# CPU.net
KiCad netlist of a schematic drawn in Altium Designer
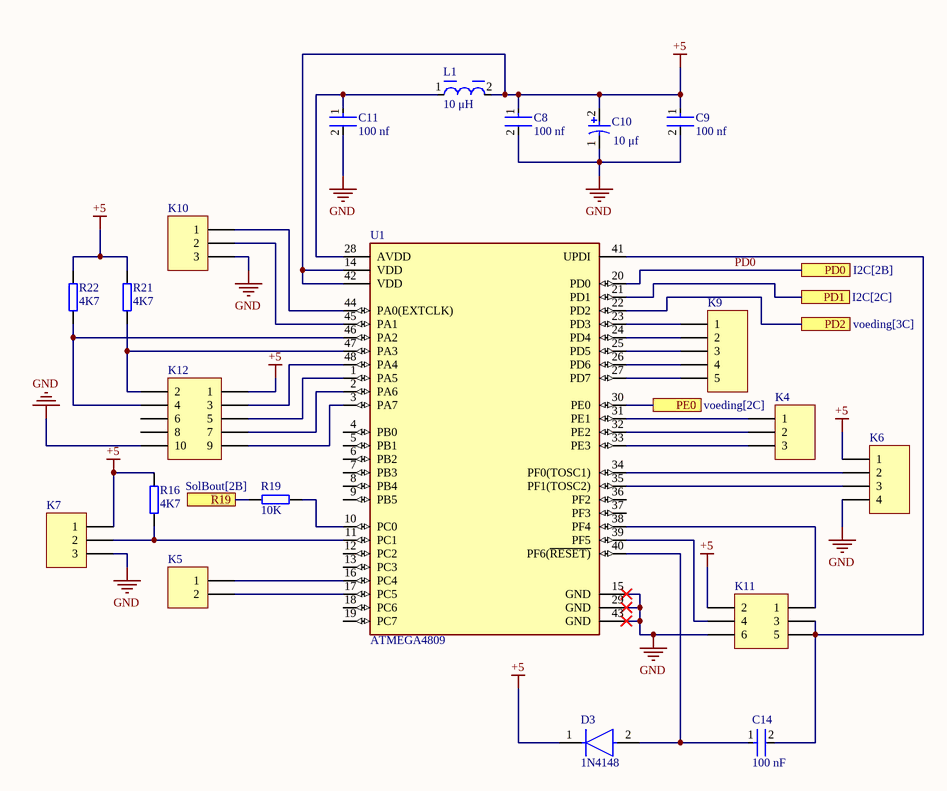
[diagram p0: CPU.SchDoc]

(export (version "E")
  (design (tool "Eeschema 10.0.6"))
  (components
    (comp (ref "C8")
      (value "100 nf")
      (footprint "CC_0805_L")
      (fields
        (field (name "MANUFACTURER") "KEMET")
        (field (name "OCTOPART") "https://octopart.com/c0805c224k5ractu-kemet-144670")
        (field (name "MANUFACTURER PART NUMBER") "C0805C224K5RACTU")
      )
      (libsource (lib "Soldeerstation_Final") (part "Capacitor_Ceramic"))
    )
    (comp (ref "C9")
      (value "100 nf")
      (footprint "CC_0805_L")
      (fields
        (field (name "MANUFACTURER") "KEMET")
        (field (name "OCTOPART") "https://octopart.com/c0805c224k5ractu-kemet-144670")
        (field (name "MANUFACTURER PART NUMBER") "C0805C224K5RACTU")
      )
      (libsource (lib "Soldeerstation_Final") (part "Capacitor_Ceramic"))
    )
    (comp (ref "C10")
      (value "10 μf")
      (footprint "CE_D8_L10")
      (fields (field (name "MANUFACTURER") "Panasonic"))
      (libsource (lib "Soldeerstation_Final") (part "Capacitor_Electrolytic"))
    )
    (comp (ref "C11")
      (value "100 nf")
      (footprint "CC_0805_L")
      (fields
        (field (name "MANUFACTURER") "KEMET")
        (field (name "OCTOPART") "https://octopart.com/c0805c224k5ractu-kemet-144670")
        (field (name "MANUFACTURER PART NUMBER") "C0805C224K5RACTU")
      )
      (libsource (lib "Soldeerstation_Final") (part "Capacitor_Ceramic"))
    )
    (comp (ref "C14")
      (value "100 nF")
      (footprint "CC_0805_L")
      (fields
        (field (name "MANUFACTURER") "KEMET")
        (field (name "OCTOPART") "https://octopart.com/c0805c224k5ractu-kemet-144670")
        (field (name "MANUFACTURER PART NUMBER") "C0805C224K5RACTU")
      )
      (libsource (lib "Soldeerstation_Final") (part "Capacitor_Ceramic"))
    )
    (comp (ref "D3")
      (value "1N4148")
      (footprint "SOD-123FL")
      (fields
        (field (name "MANUFACTURER PART NUMBER") "1N4007")
        (field (name "MANUFACTURER") "Diotec")
        (field (name "OCTOPART") "https://octopart.com/1n4007-diotec-4040411")
      )
      (libsource (lib "Soldeerstation_Final") (part "Diode"))
    )
    (comp (ref "K4")
      (value "~")
      (footprint "HDR1X3")
      (description "Header, 3-Pin")
      (fields (field (name "PUBLISHER") "Altium Limited"))
      (libsource (lib "") (part "Header 3_1"))
    )
    (comp (ref "K5")
      (value "~")
      (footprint "HDR1X2")
      (description "Header, 2-Pin")
      (fields (field (name "PUBLISHER") "Altium Limited"))
      (libsource (lib "Miscellaneous Connectors") (part "Header 2"))
    )
    (comp (ref "K6")
      (value "~")
      (footprint "HDR1X4")
      (description "Header, 4-Pin")
      (fields (field (name "PUBLISHER") "Altium Limited"))
      (libsource (lib "Miscellaneous Connectors") (part "Header 4"))
    )
    (comp (ref "K7")
      (value "~")
      (footprint "HDR1X3")
      (description "Header, 3-Pin")
      (fields (field (name "PUBLISHER") "Altium Limited"))
      (libsource (lib "Miscellaneous Connectors") (part "Header 3"))
    )
    (comp (ref "K9")
      (value "~")
      (footprint "HDR1X5")
      (description "Header, 5-Pin")
      (fields (field (name "PUBLISHER") "Altium Limited"))
      (libsource (lib "Miscellaneous Connectors") (part "Header 5"))
    )
    (comp (ref "K10")
      (value "~")
      (footprint "HDR1X3")
      (description "Header, 3-Pin")
      (fields (field (name "PUBLISHER") "Altium Limited"))
      (libsource (lib "Miscellaneous Connectors") (part "Header 3"))
    )
    (comp (ref "K11")
      (value "~")
      (footprint "HDR2X3")
      (description "Header, 3-Pin, Dual row")
      (fields (field (name "PUBLISHER") "Altium Limited"))
      (libsource (lib "Miscellaneous Connectors") (part "Header 3X2"))
    )
    (comp (ref "K12")
      (value "~")
      (footprint "HDR2X5")
      (description "Header, 5-Pin, Dual row")
      (fields (field (name "PUBLISHER") "Altium Limited"))
      (libsource (lib "Miscellaneous Connectors") (part "Header 5X2"))
    )
    (comp (ref "L1")
      (value "10 μH")
      (footprint "CC_0805_L")
      (fields (field (name "TOLERANCE") "20%"))
      (libsource (lib "Soldeerstation_Final") (part "Choke"))
    )
    (comp (ref "R16")
      (value "4K7")
      (footprint "0805_M")
      (fields (field (name "MANUFACTURER") "Vishay Dale") (field (name "PART NUMBER") "CRCW08050000Z0EA"))
      (libsource (lib "Soldeerstation_Final") (part "Resistor"))
    )
    (comp (ref "R19")
      (value "10K")
      (footprint "0805_M")
      (fields (field (name "MANUFACTURER") "Vishay Dale") (field (name "PART NUMBER") "CRCW08050000Z0EA"))
      (libsource (lib "Soldeerstation_Final") (part "Resistor"))
    )
    (comp (ref "R21")
      (value "4K7")
      (footprint "0805_M")
      (fields (field (name "MANUFACTURER") "Vishay Dale") (field (name "PART NUMBER") "CRCW08050000Z0EA"))
      (libsource (lib "Soldeerstation_Final") (part "Resistor"))
    )
    (comp (ref "R22")
      (value "4K7")
      (footprint "0805_M")
      (fields (field (name "MANUFACTURER") "Vishay Dale") (field (name "PART NUMBER") "CRCW08050000Z0EA"))
      (libsource (lib "Soldeerstation_Final") (part "Resistor"))
    )
    (comp (ref "U1")
      (value "ATMEGA4809")
      (footprint "TQFP_48_M")
      (libsource (lib "Soldeerstation_Final") (part "ATMEGA4809"))
    )
  )
  (nets
    (net (code "1") (name "+5") (class "Default")
      (node (ref "C10") (pin "2") (pinfunction "2_2") (pintype "passive"))
      (node (ref "C8") (pin "1") (pinfunction "1_1") (pintype "passive"))
      (node (ref "C9") (pin "1") (pinfunction "1_1") (pintype "passive"))
      (node (ref "D3") (pin "1") (pinfunction "C_1") (pintype "passive"))
      (node (ref "K11") (pin "2") (pinfunction "2_2") (pintype "passive"))
      (node (ref "K12") (pin "1") (pinfunction "1_1") (pintype "passive"))
      (node (ref "K6") (pin "1") (pinfunction "1_1") (pintype "passive"))
      (node (ref "K7") (pin "1") (pinfunction "1_1") (pintype "passive"))
      (node (ref "L1") (pin "2") (pinfunction "2_2") (pintype "passive"))
      (node (ref "R16") (pin "2") (pinfunction "2_2") (pintype "passive"))
      (node (ref "R21") (pin "2") (pinfunction "2_2") (pintype "passive"))
      (node (ref "R22") (pin "2") (pinfunction "2_2") (pintype "passive"))
      (node (ref "U1") (pin "14") (pinfunction "VDD_14") (pintype "power_in"))
      (node (ref "U1") (pin "42") (pinfunction "VDD_42") (pintype "power_in"))
    )
    (net (code "2") (name "/PD0") (class "Default")
      (node (ref "U1") (pin "20") (pinfunction "PD0_20") (pintype "bidirectional"))
    )
    (net (code "3") (name "/PD1") (class "Default")
      (node (ref "U1") (pin "21") (pinfunction "PD1_21") (pintype "bidirectional"))
    )
    (net (code "4") (name "/PD2") (class "Default")
      (node (ref "U1") (pin "22") (pinfunction "PD2_22") (pintype "bidirectional"))
    )
    (net (code "5") (name "/PE0") (class "Default")
      (node (ref "U1") (pin "30") (pinfunction "PE0_30") (pintype "bidirectional"))
    )
    (net (code "6") (name "/R19") (class "Default")
      (node (ref "R19") (pin "1") (pinfunction "1_1") (pintype "passive"))
    )
    (net (code "7") (name "GND") (class "Default")
      (node (ref "C10") (pin "1") (pinfunction "1_1") (pintype "passive"))
      (node (ref "C11") (pin "2") (pinfunction "2_2") (pintype "passive"))
      (node (ref "C8") (pin "2") (pinfunction "2_2") (pintype "passive"))
      (node (ref "C9") (pin "2") (pinfunction "2_2") (pintype "passive"))
      (node (ref "K10") (pin "3") (pinfunction "3_3") (pintype "passive"))
      (node (ref "K11") (pin "6") (pinfunction "6_6") (pintype "passive"))
      (node (ref "K12") (pin "10") (pinfunction "10_10") (pintype "passive"))
      (node (ref "K6") (pin "4") (pinfunction "4_4") (pintype "passive"))
      (node (ref "K7") (pin "3") (pinfunction "3_3") (pintype "passive"))
      (node (ref "U1") (pin "15") (pinfunction "GND_15") (pintype "open_emitter"))
      (node (ref "U1") (pin "29") (pinfunction "GND_29") (pintype "power_in"))
      (node (ref "U1") (pin "43") (pinfunction "GND_43") (pintype "power_in"))
    )
    (net (code "8") (name "Net-(D3-A)") (class "Default")
      (node (ref "C14") (pin "1") (pinfunction "1_1") (pintype "passive"))
      (node (ref "D3") (pin "2") (pinfunction "A_2") (pintype "passive"))
      (node (ref "U1") (pin "40") (pinfunction "PF6(~{RESET)}_40") (pintype "bidirectional"))
    )
    (net (code "9") (name "Net-(U1-AVDD)") (class "Default")
      (node (ref "C11") (pin "1") (pinfunction "1_1") (pintype "passive"))
      (node (ref "L1") (pin "1") (pinfunction "1_1") (pintype "passive"))
      (node (ref "U1") (pin "28") (pinfunction "AVDD_28") (pintype "power_in"))
    )
    (net (code "10") (name "Net-(U1-PA0(EXTCLK))") (class "Default")
      (node (ref "K10") (pin "1") (pinfunction "1_1") (pintype "passive"))
      (node (ref "U1") (pin "44") (pinfunction "PA0(EXTCLK)_44") (pintype "bidirectional"))
    )
    (net (code "11") (name "Net-(U1-PA1)") (class "Default")
      (node (ref "K10") (pin "2") (pinfunction "2_2") (pintype "passive"))
      (node (ref "U1") (pin "45") (pinfunction "PA1_45") (pintype "bidirectional"))
    )
    (net (code "12") (name "Net-(U1-PA2)") (class "Default")
      (node (ref "K12") (pin "4") (pinfunction "4_4") (pintype "passive"))
      (node (ref "R22") (pin "1") (pinfunction "1_1") (pintype "passive"))
      (node (ref "U1") (pin "46") (pinfunction "PA2_46") (pintype "bidirectional"))
    )
    (net (code "13") (name "Net-(U1-PA3)") (class "Default")
      (node (ref "K12") (pin "2") (pinfunction "2_2") (pintype "passive"))
      (node (ref "R21") (pin "1") (pinfunction "1_1") (pintype "passive"))
      (node (ref "U1") (pin "47") (pinfunction "PA3_47") (pintype "bidirectional"))
    )
    (net (code "14") (name "Net-(U1-PA4)") (class "Default")
      (node (ref "K12") (pin "3") (pinfunction "3_3") (pintype "passive"))
      (node (ref "U1") (pin "48") (pinfunction "PA4_48") (pintype "bidirectional"))
    )
    (net (code "15") (name "Net-(U1-PA5)") (class "Default")
      (node (ref "K12") (pin "5") (pinfunction "5_5") (pintype "passive"))
      (node (ref "U1") (pin "1") (pinfunction "PA5_1") (pintype "bidirectional"))
    )
    (net (code "16") (name "Net-(U1-PA6)") (class "Default")
      (node (ref "K12") (pin "7") (pinfunction "7_7") (pintype "passive"))
      (node (ref "U1") (pin "2") (pinfunction "PA6_2") (pintype "bidirectional"))
    )
    (net (code "17") (name "Net-(U1-PA7)") (class "Default")
      (node (ref "K12") (pin "9") (pinfunction "9_9") (pintype "passive"))
      (node (ref "U1") (pin "3") (pinfunction "PA7_3") (pintype "bidirectional"))
    )
    (net (code "18") (name "Net-(U1-PC0)") (class "Default")
      (node (ref "R19") (pin "2") (pinfunction "2_2") (pintype "passive"))
      (node (ref "U1") (pin "10") (pinfunction "PC0_10") (pintype "bidirectional"))
    )
    (net (code "19") (name "Net-(U1-PC1)") (class "Default")
      (node (ref "K7") (pin "2") (pinfunction "2_2") (pintype "passive"))
      (node (ref "R16") (pin "1") (pinfunction "1_1") (pintype "passive"))
      (node (ref "U1") (pin "11") (pinfunction "PC1_11") (pintype "bidirectional"))
    )
    (net (code "20") (name "Net-(U1-PC4)") (class "Default")
      (node (ref "K5") (pin "1") (pinfunction "1_1") (pintype "passive"))
      (node (ref "U1") (pin "16") (pinfunction "PC4_16") (pintype "bidirectional"))
    )
    (net (code "21") (name "Net-(U1-PC5)") (class "Default")
      (node (ref "K5") (pin "2") (pinfunction "2_2") (pintype "passive"))
      (node (ref "U1") (pin "17") (pinfunction "PC5_17") (pintype "bidirectional"))
    )
    (net (code "22") (name "Net-(U1-PD3)") (class "Default")
      (node (ref "K9") (pin "1") (pinfunction "1_1") (pintype "passive"))
      (node (ref "U1") (pin "23") (pinfunction "PD3_23") (pintype "bidirectional"))
    )
    (net (code "23") (name "Net-(U1-PD4)") (class "Default")
      (node (ref "K9") (pin "2") (pinfunction "2_2") (pintype "passive"))
      (node (ref "U1") (pin "24") (pinfunction "PD4_24") (pintype "bidirectional"))
    )
    (net (code "24") (name "Net-(U1-PD5)") (class "Default")
      (node (ref "K9") (pin "3") (pinfunction "3_3") (pintype "passive"))
      (node (ref "U1") (pin "25") (pinfunction "PD5_25") (pintype "bidirectional"))
    )
    (net (code "25") (name "Net-(U1-PD6)") (class "Default")
      (node (ref "K9") (pin "4") (pinfunction "4_4") (pintype "passive"))
      (node (ref "U1") (pin "26") (pinfunction "PD6_26") (pintype "bidirectional"))
    )
    (net (code "26") (name "Net-(U1-PD7)") (class "Default")
      (node (ref "K9") (pin "5") (pinfunction "5_5") (pintype "passive"))
      (node (ref "U1") (pin "27") (pinfunction "PD7_27") (pintype "bidirectional"))
    )
    (net (code "27") (name "Net-(U1-PE1)") (class "Default")
      (node (ref "K4") (pin "1") (pinfunction "1_1") (pintype "passive"))
      (node (ref "U1") (pin "31") (pinfunction "PE1_31") (pintype "bidirectional"))
    )
    (net (code "28") (name "Net-(U1-PE2)") (class "Default")
      (node (ref "K4") (pin "2") (pinfunction "2_2") (pintype "passive"))
      (node (ref "U1") (pin "32") (pinfunction "PE2_32") (pintype "bidirectional"))
    )
    (net (code "29") (name "Net-(U1-PE3)") (class "Default")
      (node (ref "K4") (pin "3") (pinfunction "3_3") (pintype "passive"))
      (node (ref "U1") (pin "33") (pinfunction "PE3_33") (pintype "bidirectional"))
    )
    (net (code "30") (name "Net-(U1-PF0(TOSC1))") (class "Default")
      (node (ref "K6") (pin "2") (pinfunction "2_2") (pintype "passive"))
      (node (ref "U1") (pin "34") (pinfunction "PF0(TOSC1)_34") (pintype "bidirectional"))
    )
    (net (code "31") (name "Net-(U1-PF1(TOSC2))") (class "Default")
      (node (ref "K6") (pin "3") (pinfunction "3_3") (pintype "passive"))
      (node (ref "U1") (pin "35") (pinfunction "PF1(TOSC2)_35") (pintype "bidirectional"))
    )
    (net (code "32") (name "Net-(U1-PF4)") (class "Default")
      (node (ref "K11") (pin "1") (pinfunction "1_1") (pintype "passive"))
      (node (ref "U1") (pin "38") (pinfunction "PF4_38") (pintype "bidirectional"))
    )
    (net (code "33") (name "Net-(U1-PF5)") (class "Default")
      (node (ref "K11") (pin "4") (pinfunction "4_4") (pintype "passive"))
      (node (ref "U1") (pin "39") (pinfunction "PF5_39") (pintype "bidirectional"))
    )
    (net (code "34") (name "Net-(U1-UPDI)") (class "Default")
      (node (ref "C14") (pin "2") (pinfunction "2_2") (pintype "passive"))
      (node (ref "K11") (pin "3") (pinfunction "3_3") (pintype "passive"))
      (node (ref "K11") (pin "5") (pinfunction "5_5") (pintype "passive"))
      (node (ref "U1") (pin "41") (pinfunction "UPDI_41") (pintype "passive"))
    )
    (net (code "35") (name "unconnected-(K12-Pad6)") (class "Default")
      (node (ref "K12") (pin "6") (pinfunction "6_6") (pintype "passive"))
    )
    (net (code "36") (name "unconnected-(K12-Pad8)") (class "Default")
      (node (ref "K12") (pin "8") (pinfunction "8_8") (pintype "passive"))
    )
    (net (code "37") (name "unconnected-(U1-PB0-Pad4)") (class "Default")
      (node (ref "U1") (pin "4") (pinfunction "PB0_4") (pintype "bidirectional"))
    )
    (net (code "38") (name "unconnected-(U1-PB1-Pad5)") (class "Default")
      (node (ref "U1") (pin "5") (pinfunction "PB1_5") (pintype "bidirectional"))
    )
    (net (code "39") (name "unconnected-(U1-PB2-Pad6)") (class "Default")
      (node (ref "U1") (pin "6") (pinfunction "PB2_6") (pintype "bidirectional"))
    )
    (net (code "40") (name "unconnected-(U1-PB3-Pad7)") (class "Default")
      (node (ref "U1") (pin "7") (pinfunction "PB3_7") (pintype "bidirectional"))
    )
    (net (code "41") (name "unconnected-(U1-PB4-Pad8)") (class "Default")
      (node (ref "U1") (pin "8") (pinfunction "PB4_8") (pintype "bidirectional"))
    )
    (net (code "42") (name "unconnected-(U1-PB5-Pad9)") (class "Default")
      (node (ref "U1") (pin "9") (pinfunction "PB5_9") (pintype "bidirectional"))
    )
    (net (code "43") (name "unconnected-(U1-PC2-Pad12)") (class "Default")
      (node (ref "U1") (pin "12") (pinfunction "PC2_12") (pintype "bidirectional"))
    )
    (net (code "44") (name "unconnected-(U1-PC3-Pad13)") (class "Default")
      (node (ref "U1") (pin "13") (pinfunction "PC3_13") (pintype "bidirectional"))
    )
    (net (code "45") (name "unconnected-(U1-PC6-Pad18)") (class "Default")
      (node (ref "U1") (pin "18") (pinfunction "PC6_18") (pintype "bidirectional"))
    )
    (net (code "46") (name "unconnected-(U1-PC7-Pad19)") (class "Default")
      (node (ref "U1") (pin "19") (pinfunction "PC7_19") (pintype "bidirectional"))
    )
    (net (code "47") (name "unconnected-(U1-PF2-Pad36)") (class "Default")
      (node (ref "U1") (pin "36") (pinfunction "PF2_36") (pintype "bidirectional"))
    )
    (net (code "48") (name "unconnected-(U1-PF3-Pad37)") (class "Default")
      (node (ref "U1") (pin "37") (pinfunction "PF3_37") (pintype "bidirectional"))
    )
  )
)
